# PCB_Siren.net
KiCad netlist of a schematic drawn in Altium Designer
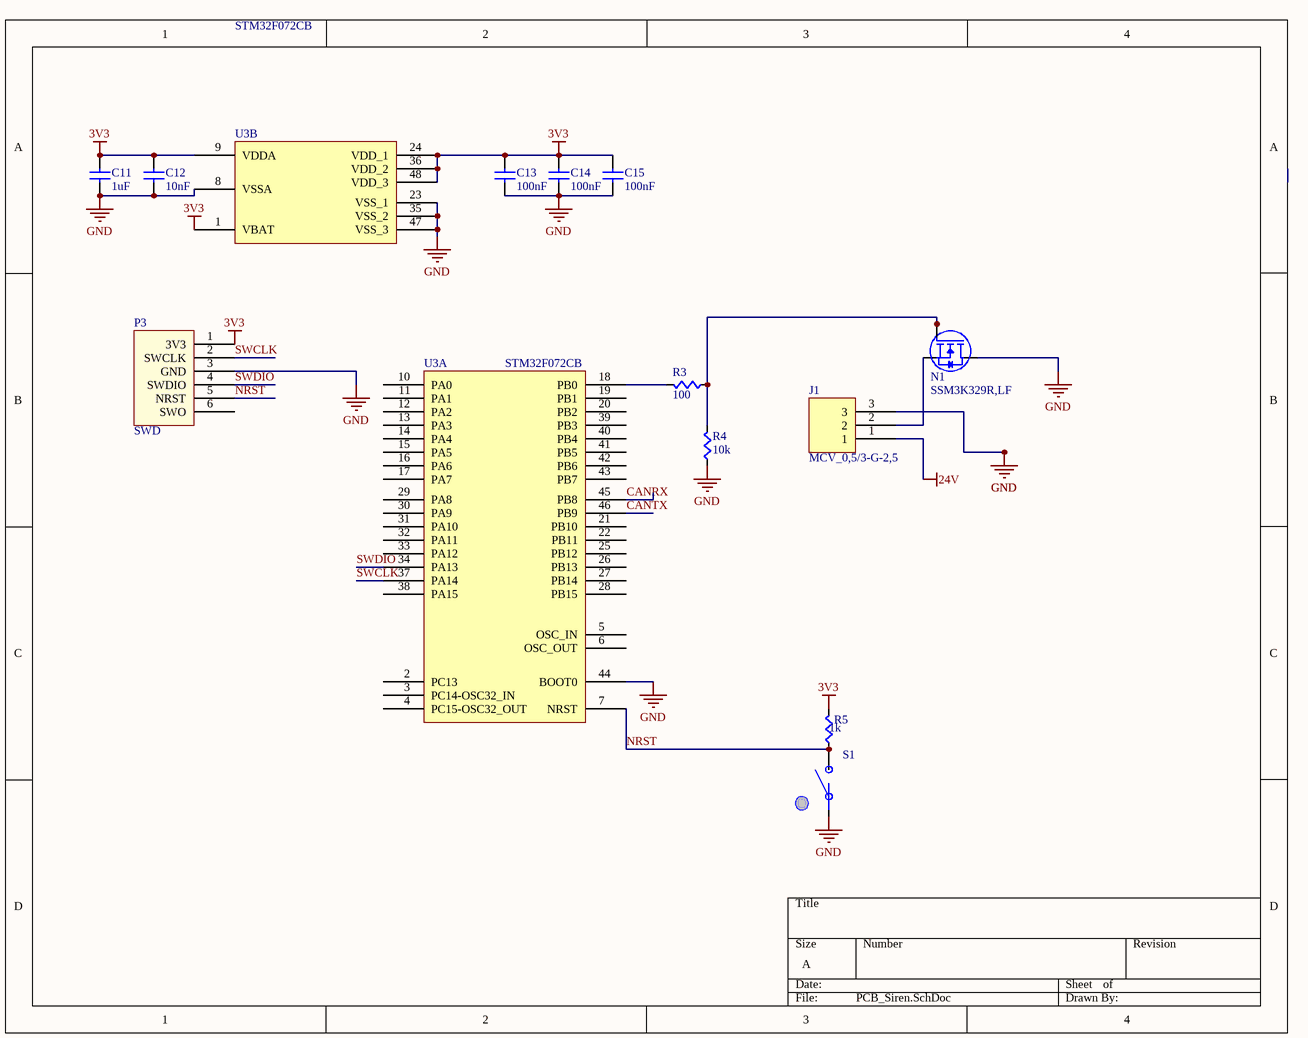
[diagram p0: PCB_Siren.SchDoc]

(export (version "E")
  (design (tool "Eeschema 10.0.6"))
  (components
    (comp (ref "C11")
      (value "1uF")
      (footprint "CAPC0603")
      (fields (field (name "Comment") "Cap"))
      (libsource (lib "SubjuGator8") (part "Cap"))
    )
    (comp (ref "C12")
      (value "10nF")
      (footprint "CAPC0603")
      (fields (field (name "Comment") "Cap"))
      (libsource (lib "SubjuGator8") (part "Cap"))
    )
    (comp (ref "C13")
      (value "100nF")
      (footprint "CAPC0603")
      (fields (field (name "Comment") "Cap"))
      (libsource (lib "SubjuGator8") (part "Cap"))
    )
    (comp (ref "C14")
      (value "100nF")
      (footprint "CAPC0603")
      (fields (field (name "Comment") "Cap"))
      (libsource (lib "SubjuGator8") (part "Cap"))
    )
    (comp (ref "C15")
      (value "100nF")
      (footprint "CAPC0603")
      (fields (field (name "Comment") "Cap"))
      (libsource (lib "SubjuGator8") (part "Cap"))
    )
    (comp (ref "J1")
      (value "MCV_0,5/3-G-2,5")
      (footprint "MCV_0,5/3-G-2,5")
      (description "CONN TERM BLOCK 2.50MM 3POS, Vertical, Through-Hole, 4A")
      (libsource (lib "SubjuGator8") (part "MCV_0,5/3-G-2,5"))
    )
    (comp (ref "N1")
      (value "SSM3K329R,LF")
      (footprint "Semiconductors:SSM3K329R,LF")
      (description "MOSFET N CH 30V 3.5A 2-3Z1A")
      (libsource (lib "SubjuGator8") (part "SSM3K329R,LF"))
    )
    (comp (ref "P3")
      (value "SWD")
      (footprint "SWD_STM32")
      (description "SWD connector matching the pinout on STM Discovery Boards")
      (libsource (lib "SubjuGator8") (part "SWD_STM32"))
    )
    (comp (ref "R3")
      (value "100")
      (footprint "RES0603")
      (fields (field (name "Comment") "Res"))
      (libsource (lib "SubjuGator8") (part "Res"))
    )
    (comp (ref "R4")
      (value "10k")
      (footprint "RES0603")
      (fields (field (name "Comment") "Res"))
      (libsource (lib "SubjuGator8") (part "Res"))
    )
    (comp (ref "R5")
      (value "1k")
      (footprint "RES0603")
      (fields (field (name "Comment") "Res"))
      (libsource (lib "SubjuGator8") (part "Res"))
    )
    (comp (ref "S1")
      (value "Button")
      (footprint "PTS645xxxxSMTR92")
      (description "SPST Button")
      (libsource (lib "SubjuGator8") (part "Button"))
    )
    (comp (ref "U3")
      (value "STM32F072CB")
      (footprint "STM32F072CB")
      (description "MCU 32BIT 128KB FLASH 48LQFP")
      (libsource (lib "SubjuGator8") (part "STM32F072CB"))
    )
  )
  (nets
    (net (code "1") (name "/CANRX") (class "Default")
      (node (ref "U3") (pin "45") (pinfunction "PB8_45") (pintype "passive"))
    )
    (net (code "2") (name "/CANTX") (class "Default")
      (node (ref "U3") (pin "46") (pinfunction "PB9_46") (pintype "passive"))
    )
    (net (code "3") (name "/NRST") (class "Default")
      (node (ref "P3") (pin "5") (pinfunction "NRST_5") (pintype "passive"))
      (node (ref "R5") (pin "2") (pinfunction "B_2") (pintype "passive"))
      (node (ref "S1") (pin "B") (pinfunction "B_B") (pintype "passive"))
      (node (ref "U3") (pin "7") (pinfunction "NRST_7") (pintype "passive"))
    )
    (net (code "4") (name "/SWCLK") (class "Default")
      (node (ref "P3") (pin "2") (pinfunction "SWCLK_2") (pintype "passive"))
      (node (ref "U3") (pin "37") (pinfunction "PA14_37") (pintype "passive"))
    )
    (net (code "5") (name "/SWDIO") (class "Default")
      (node (ref "P3") (pin "4") (pinfunction "SWDIO_4") (pintype "passive"))
      (node (ref "U3") (pin "34") (pinfunction "PA13_34") (pintype "passive"))
    )
    (net (code "6") (name "3V3") (class "Default")
      (node (ref "C11") (pin "1") (pinfunction "A_1") (pintype "passive"))
      (node (ref "C12") (pin "1") (pinfunction "A_1") (pintype "passive"))
      (node (ref "C13") (pin "1") (pinfunction "A_1") (pintype "passive"))
      (node (ref "C14") (pin "1") (pinfunction "A_1") (pintype "passive"))
      (node (ref "C15") (pin "1") (pinfunction "A_1") (pintype "passive"))
      (node (ref "P3") (pin "1") (pinfunction "3V3_1") (pintype "passive"))
      (node (ref "R5") (pin "1") (pinfunction "A_1") (pintype "passive"))
      (node (ref "U3") (pin "1") (pinfunction "VBAT_1") (pintype "passive"))
      (node (ref "U3") (pin "24") (pinfunction "VDD_1_24") (pintype "passive"))
      (node (ref "U3") (pin "36") (pinfunction "VDD_2_36") (pintype "passive"))
      (node (ref "U3") (pin "48") (pinfunction "VDD_3_48") (pintype "passive"))
      (node (ref "U3") (pin "9") (pinfunction "VDDA_9") (pintype "passive"))
    )
    (net (code "7") (name "24V") (class "Default")
      (node (ref "J1") (pin "1") (pinfunction "1_1") (pintype "passive"))
    )
    (net (code "8") (name "GND") (class "Default")
      (node (ref "C11") (pin "2") (pinfunction "B_2") (pintype "passive"))
      (node (ref "C12") (pin "2") (pinfunction "B_2") (pintype "passive"))
      (node (ref "C13") (pin "2") (pinfunction "B_2") (pintype "passive"))
      (node (ref "C14") (pin "2") (pinfunction "B_2") (pintype "passive"))
      (node (ref "C15") (pin "2") (pinfunction "B_2") (pintype "passive"))
      (node (ref "J1") (pin "3") (pinfunction "3_3") (pintype "passive"))
      (node (ref "N1") (pin "3") (pinfunction "D_3") (pintype "passive"))
      (node (ref "P3") (pin "3") (pinfunction "GND_3") (pintype "passive"))
      (node (ref "R4") (pin "2") (pinfunction "B_2") (pintype "passive"))
      (node (ref "S1") (pin "A") (pinfunction "A_A") (pintype "passive"))
      (node (ref "U3") (pin "23") (pinfunction "VSS_1_23") (pintype "passive"))
      (node (ref "U3") (pin "35") (pinfunction "VSS_2_35") (pintype "passive"))
      (node (ref "U3") (pin "44") (pinfunction "BOOT0_44") (pintype "passive"))
      (node (ref "U3") (pin "47") (pinfunction "VSS_3_47") (pintype "passive"))
      (node (ref "U3") (pin "8") (pinfunction "VSSA_8") (pintype "passive"))
    )
    (net (code "9") (name "Net-(N1-G)") (class "Default")
      (node (ref "N1") (pin "1") (pinfunction "G_1") (pintype "passive"))
      (node (ref "R3") (pin "2") (pinfunction "B_2") (pintype "passive"))
      (node (ref "R4") (pin "1") (pinfunction "A_1") (pintype "passive"))
    )
    (net (code "10") (name "Net-(N1-S)") (class "Default")
      (node (ref "J1") (pin "2") (pinfunction "2_2") (pintype "passive"))
      (node (ref "N1") (pin "2") (pinfunction "S_2") (pintype "passive"))
    )
    (net (code "11") (name "Net-(R3-A)") (class "Default")
      (node (ref "R3") (pin "1") (pinfunction "A_1") (pintype "passive"))
      (node (ref "U3") (pin "18") (pinfunction "PB0_18") (pintype "passive"))
    )
    (net (code "12") (name "unconnected-(P3-SWO-Pad6)") (class "Default")
      (node (ref "P3") (pin "6") (pinfunction "SWO_6") (pintype "passive"))
    )
    (net (code "13") (name "unconnected-(U3A-OSC_IN-Pad5)") (class "Default")
      (node (ref "U3") (pin "5") (pinfunction "OSC_IN_5") (pintype "passive"))
    )
    (net (code "14") (name "unconnected-(U3A-OSC_OUT-Pad6)") (class "Default")
      (node (ref "U3") (pin "6") (pinfunction "OSC_OUT_6") (pintype "passive"))
    )
    (net (code "15") (name "unconnected-(U3A-PA0-Pad10)") (class "Default")
      (node (ref "U3") (pin "10") (pinfunction "PA0_10") (pintype "passive"))
    )
    (net (code "16") (name "unconnected-(U3A-PA1-Pad11)") (class "Default")
      (node (ref "U3") (pin "11") (pinfunction "PA1_11") (pintype "passive"))
    )
    (net (code "17") (name "unconnected-(U3A-PA2-Pad12)") (class "Default")
      (node (ref "U3") (pin "12") (pinfunction "PA2_12") (pintype "passive"))
    )
    (net (code "18") (name "unconnected-(U3A-PA3-Pad13)") (class "Default")
      (node (ref "U3") (pin "13") (pinfunction "PA3_13") (pintype "passive"))
    )
    (net (code "19") (name "unconnected-(U3A-PA4-Pad14)") (class "Default")
      (node (ref "U3") (pin "14") (pinfunction "PA4_14") (pintype "passive"))
    )
    (net (code "20") (name "unconnected-(U3A-PA5-Pad15)") (class "Default")
      (node (ref "U3") (pin "15") (pinfunction "PA5_15") (pintype "passive"))
    )
    (net (code "21") (name "unconnected-(U3A-PA6-Pad16)") (class "Default")
      (node (ref "U3") (pin "16") (pinfunction "PA6_16") (pintype "passive"))
    )
    (net (code "22") (name "unconnected-(U3A-PA7-Pad17)") (class "Default")
      (node (ref "U3") (pin "17") (pinfunction "PA7_17") (pintype "passive"))
    )
    (net (code "23") (name "unconnected-(U3A-PA8-Pad29)") (class "Default")
      (node (ref "U3") (pin "29") (pinfunction "PA8_29") (pintype "passive"))
    )
    (net (code "24") (name "unconnected-(U3A-PA9-Pad30)") (class "Default")
      (node (ref "U3") (pin "30") (pinfunction "PA9_30") (pintype "passive"))
    )
    (net (code "25") (name "unconnected-(U3A-PA10-Pad31)") (class "Default")
      (node (ref "U3") (pin "31") (pinfunction "PA10_31") (pintype "passive"))
    )
    (net (code "26") (name "unconnected-(U3A-PA11-Pad32)") (class "Default")
      (node (ref "U3") (pin "32") (pinfunction "PA11_32") (pintype "passive"))
    )
    (net (code "27") (name "unconnected-(U3A-PA12-Pad33)") (class "Default")
      (node (ref "U3") (pin "33") (pinfunction "PA12_33") (pintype "passive"))
    )
    (net (code "28") (name "unconnected-(U3A-PA15-Pad38)") (class "Default")
      (node (ref "U3") (pin "38") (pinfunction "PA15_38") (pintype "passive"))
    )
    (net (code "29") (name "unconnected-(U3A-PB1-Pad19)") (class "Default")
      (node (ref "U3") (pin "19") (pinfunction "PB1_19") (pintype "passive"))
    )
    (net (code "30") (name "unconnected-(U3A-PB2-Pad20)") (class "Default")
      (node (ref "U3") (pin "20") (pinfunction "PB2_20") (pintype "passive"))
    )
    (net (code "31") (name "unconnected-(U3A-PB3-Pad39)") (class "Default")
      (node (ref "U3") (pin "39") (pinfunction "PB3_39") (pintype "passive"))
    )
    (net (code "32") (name "unconnected-(U3A-PB4-Pad40)") (class "Default")
      (node (ref "U3") (pin "40") (pinfunction "PB4_40") (pintype "passive"))
    )
    (net (code "33") (name "unconnected-(U3A-PB5-Pad41)") (class "Default")
      (node (ref "U3") (pin "41") (pinfunction "PB5_41") (pintype "passive"))
    )
    (net (code "34") (name "unconnected-(U3A-PB6-Pad42)") (class "Default")
      (node (ref "U3") (pin "42") (pinfunction "PB6_42") (pintype "passive"))
    )
    (net (code "35") (name "unconnected-(U3A-PB7-Pad43)") (class "Default")
      (node (ref "U3") (pin "43") (pinfunction "PB7_43") (pintype "passive"))
    )
    (net (code "36") (name "unconnected-(U3A-PB10-Pad21)") (class "Default")
      (node (ref "U3") (pin "21") (pinfunction "PB10_21") (pintype "passive"))
    )
    (net (code "37") (name "unconnected-(U3A-PB11-Pad22)") (class "Default")
      (node (ref "U3") (pin "22") (pinfunction "PB11_22") (pintype "passive"))
    )
    (net (code "38") (name "unconnected-(U3A-PB12-Pad25)") (class "Default")
      (node (ref "U3") (pin "25") (pinfunction "PB12_25") (pintype "passive"))
    )
    (net (code "39") (name "unconnected-(U3A-PB13-Pad26)") (class "Default")
      (node (ref "U3") (pin "26") (pinfunction "PB13_26") (pintype "passive"))
    )
    (net (code "40") (name "unconnected-(U3A-PB14-Pad27)") (class "Default")
      (node (ref "U3") (pin "27") (pinfunction "PB14_27") (pintype "passive"))
    )
    (net (code "41") (name "unconnected-(U3A-PB15-Pad28)") (class "Default")
      (node (ref "U3") (pin "28") (pinfunction "PB15_28") (pintype "passive"))
    )
    (net (code "42") (name "unconnected-(U3A-PC13-Pad2)") (class "Default")
      (node (ref "U3") (pin "2") (pinfunction "PC13_2") (pintype "passive"))
    )
    (net (code "43") (name "unconnected-(U3A-PC14-OSC32_IN-Pad3)") (class "Default")
      (node (ref "U3") (pin "3") (pinfunction "PC14-OSC32_IN_3") (pintype "passive"))
    )
    (net (code "44") (name "unconnected-(U3A-PC15-OSC32_OUT-Pad4)") (class "Default")
      (node (ref "U3") (pin "4") (pinfunction "PC15-OSC32_OUT_4") (pintype "passive"))
    )
  )
)
